# Intar_Button_Module.net
KiCad netlist of a schematic drawn in EAGLE
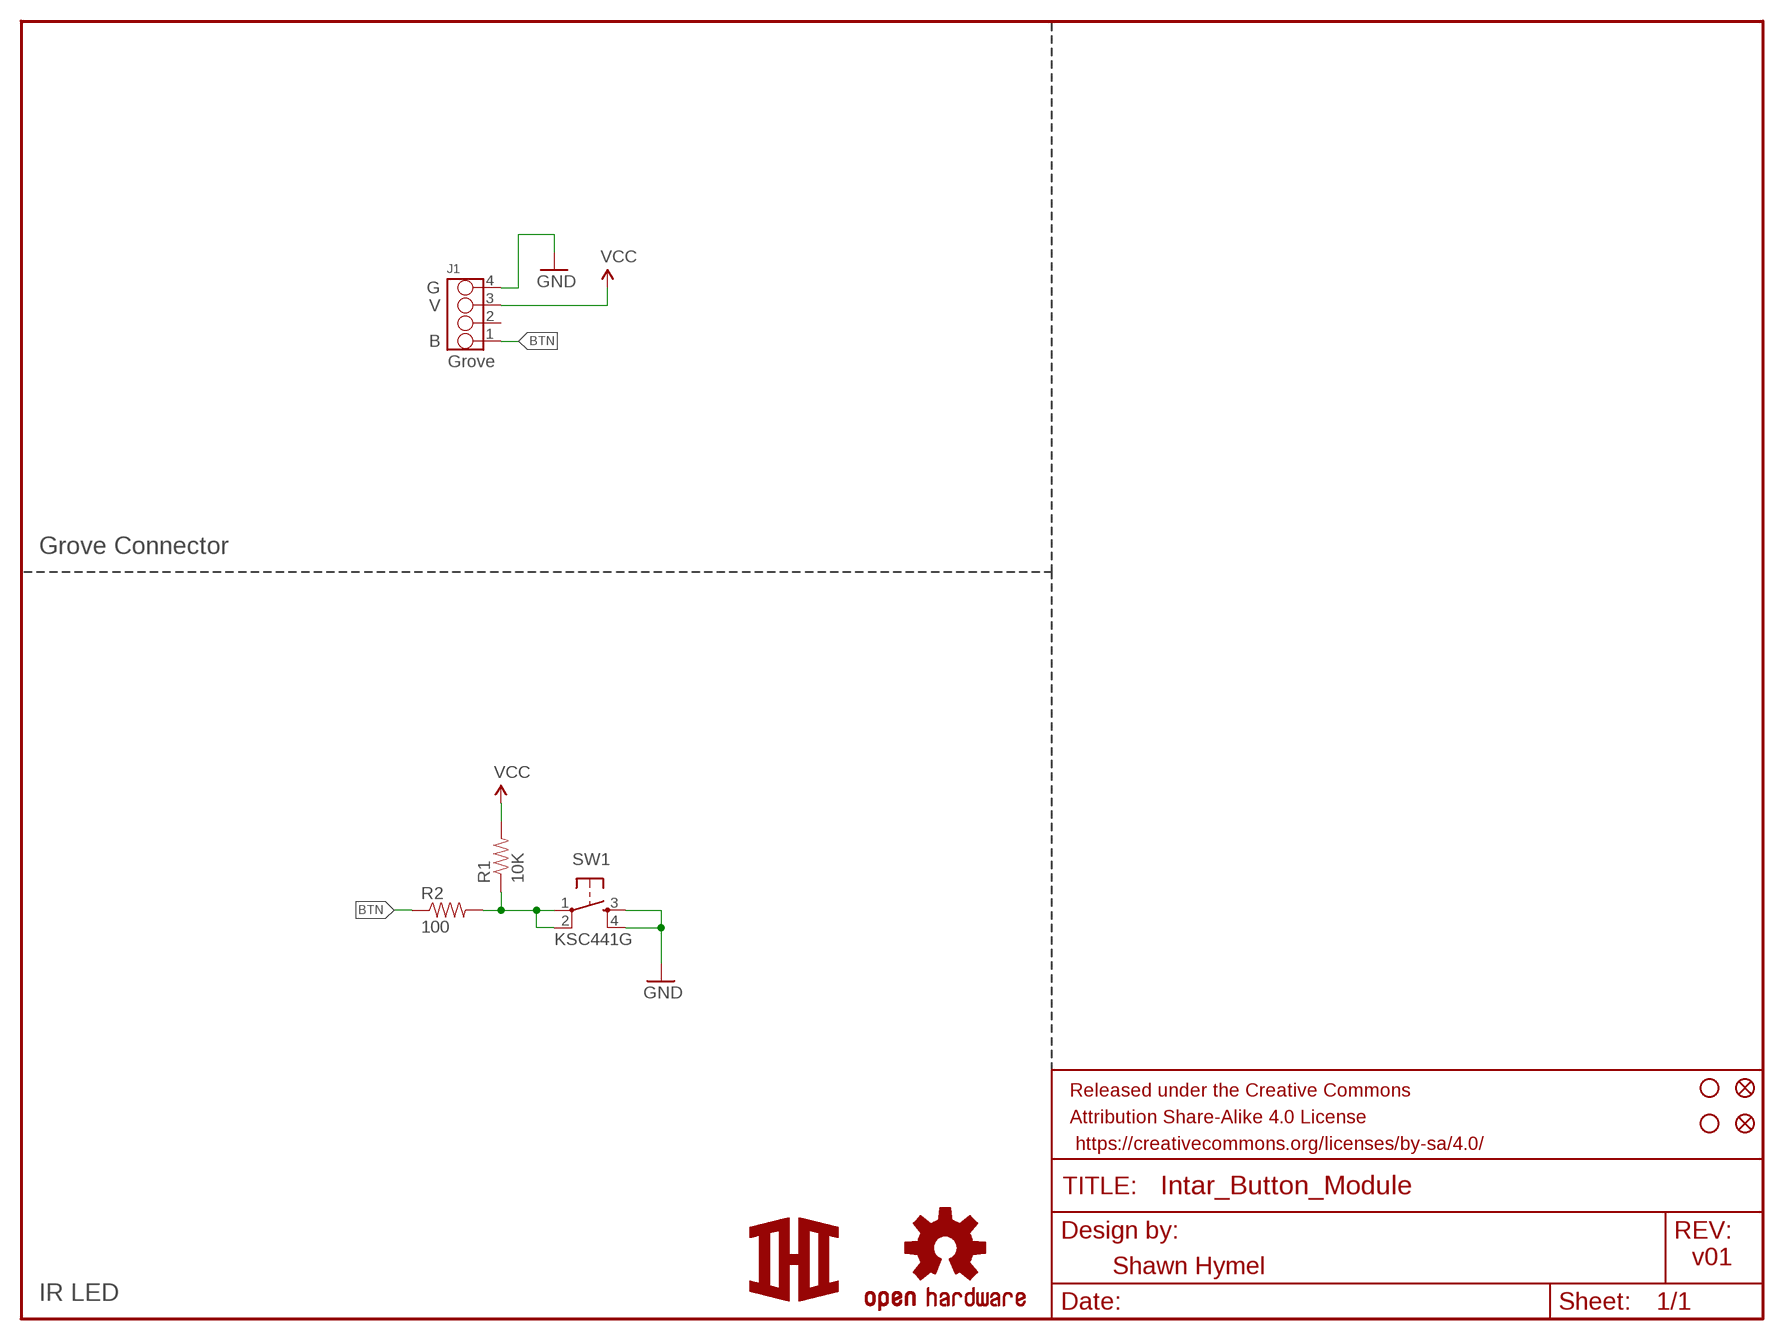
[diagram p0: schematic, sheet 1]

(export (version "E")
  (design (tool "Eeschema 10.0.6"))
  (components
    (comp (ref "FID1")
      (value "FIDUCIAL1X2")
      (footprint "eagle-import:FIDUCIAL-1X2")
      (libsource (lib "eagle-import") (part "FIDUCIAL1X2"))
    )
    (comp (ref "FID2")
      (value "FIDUCIAL1X2")
      (footprint "eagle-import:FIDUCIAL-1X2")
      (libsource (lib "eagle-import") (part "FIDUCIAL1X2"))
    )
    (comp (ref "FRAME1")
      (value "FRAME-LETTER")
      (footprint "eagle-import:CREATIVE_COMMONS")
      (libsource (lib "eagle-import") (part "FRAME-LETTER"))
    )
    (comp (ref "J1")
      (value "GROVE-4P-2.0-3470130P1")
      (footprint "eagle-import:4P-2.0")
      (libsource (lib "eagle-import") (part "GROVE-4P-2.0-3470130P1"))
    )
    (comp (ref "LOGO1")
      (value "OSHW-LOGOS")
      (footprint "eagle-import:OSHW-LOGO-S")
      (libsource (lib "eagle-import") (part "OSHW-LOGOS"))
    )
    (comp (ref "R1")
      (value "10K")
      (footprint "eagle-import:0603-RES")
      (libsource (lib "eagle-import") (part "10KOHM-1/10W-1%(0603)0603"))
    )
    (comp (ref "R2")
      (value "100")
      (footprint "eagle-import:0603-RES")
      (libsource (lib "eagle-import") (part "100OHM-1/10W-1%(0603)"))
    )
    (comp (ref "STANDOFF1")
      (value "STAND-OFF")
      (footprint "eagle-import:STAND-OFF")
      (libsource (lib "eagle-import") (part "STAND-OFF"))
    )
    (comp (ref "STANDOFF2")
      (value "STAND-OFF")
      (footprint "eagle-import:STAND-OFF")
      (libsource (lib "eagle-import") (part "STAND-OFF"))
    )
    (comp (ref "SW1")
      (value "SWITCH_MOMENTARY")
      (footprint "eagle-import:KSCXXXG")
      (libsource (lib "eagle-import") (part "SWITCH_MOMENTARY"))
    )
    (comp (ref "U$1")
      (value "LOGOSM")
      (footprint "eagle-import:LOGO_SM")
      (libsource (lib "eagle-import") (part "LOGOSM"))
    )
  )
  (nets
    (net (code "1") (name "BTN") (class "Default")
      (node (ref "J1") (pin "1") (pinfunction "1_1") (pintype "bidirectional"))
      (node (ref "R2") (pin "1") (pinfunction "1_1") (pintype "passive"))
    )
    (net (code "2") (name "GND") (class "Default")
      (node (ref "J1") (pin "4") (pinfunction "4_4") (pintype "bidirectional"))
      (node (ref "SW1") (pin "3") (pinfunction "3_3") (pintype "passive"))
      (node (ref "SW1") (pin "4") (pinfunction "4_4") (pintype "passive"))
    )
    (net (code "3") (name "Net-(R1-Pad1)") (class "Default")
      (node (ref "R1") (pin "1") (pinfunction "1_1") (pintype "passive"))
      (node (ref "R2") (pin "2") (pinfunction "2_2") (pintype "passive"))
      (node (ref "SW1") (pin "1") (pinfunction "1_1") (pintype "passive"))
      (node (ref "SW1") (pin "2") (pinfunction "2_2") (pintype "passive"))
    )
    (net (code "4") (name "VCC") (class "Default")
      (node (ref "J1") (pin "3") (pinfunction "3_3") (pintype "bidirectional"))
      (node (ref "R1") (pin "2") (pinfunction "2_2") (pintype "passive"))
    )
    (net (code "5") (name "unconnected-(J1-Pad2)") (class "Default")
      (node (ref "J1") (pin "2") (pinfunction "2_2") (pintype "bidirectional"))
    )
  )
)
